# UI_mon.net
KiCad netlist of a schematic drawn in Altium Designer
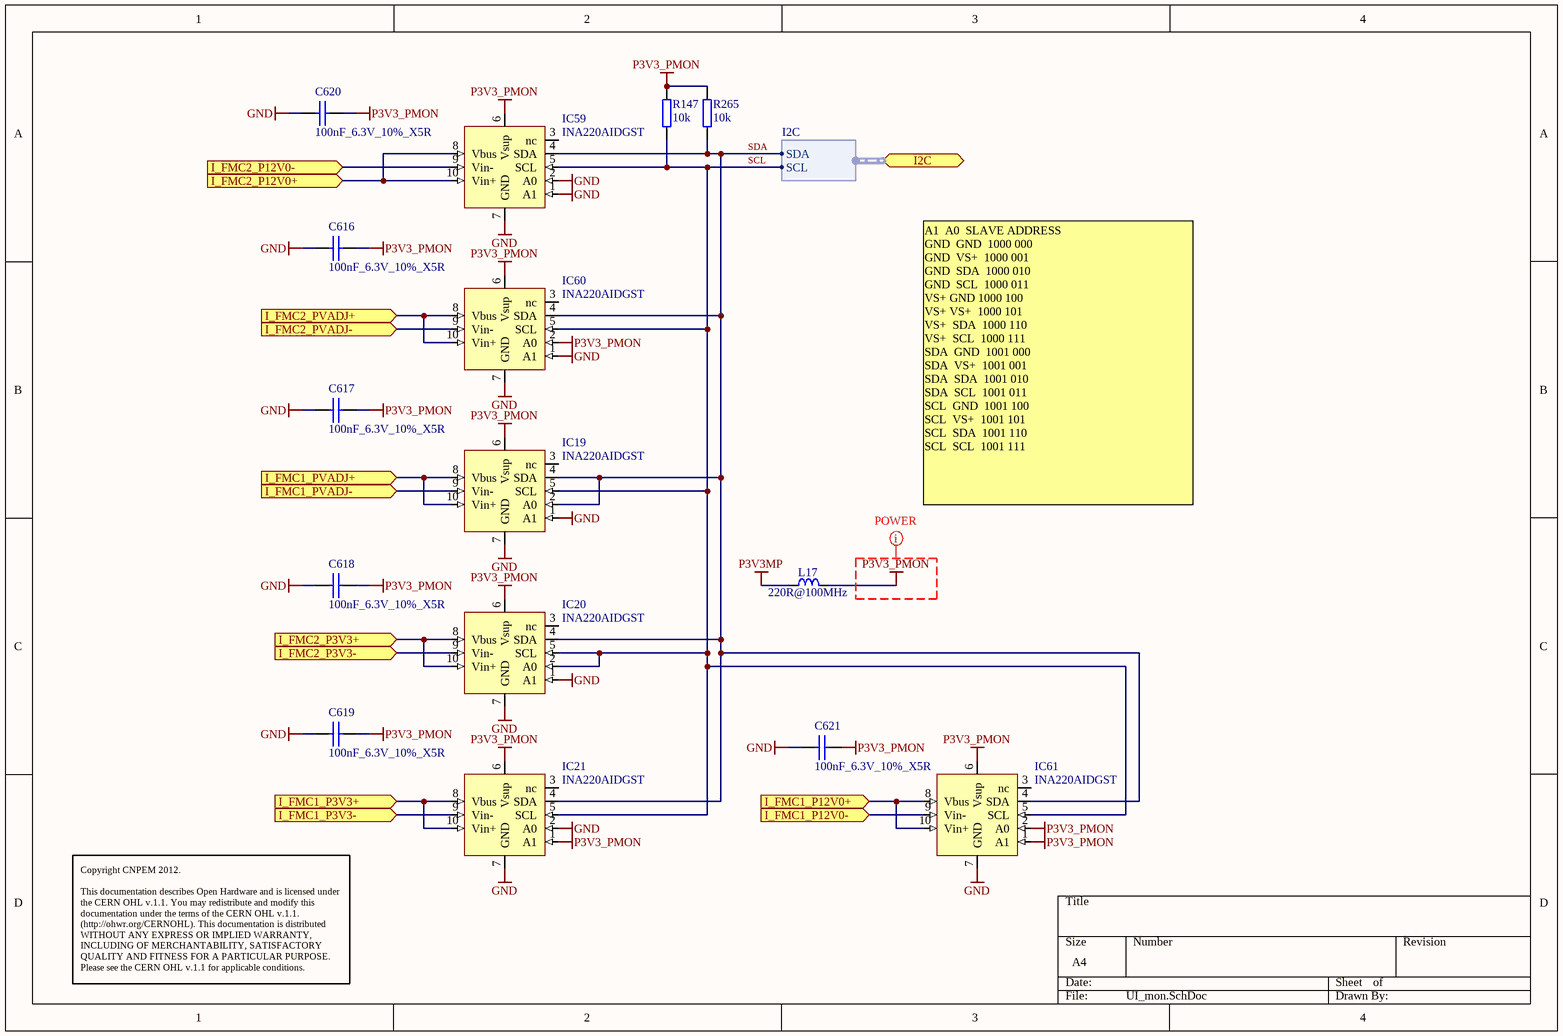
[diagram p0: UI_mon.SchDoc]

(export (version "E")
  (design (tool "Eeschema 10.0.6"))
  (components
    (comp (ref "C616")
      (value "100nF_6.3V_10%_X5R")
      (footprint "0201C")
      (description "Capacitor SMD")
      (libsource (lib "LIBRARY_SCH") (part "CAP_SMD_0201"))
    )
    (comp (ref "C617")
      (value "100nF_6.3V_10%_X5R")
      (footprint "0201C")
      (description "Capacitor SMD")
      (libsource (lib "LIBRARY_SCH") (part "CAP_SMD_0201"))
    )
    (comp (ref "C618")
      (value "100nF_6.3V_10%_X5R")
      (footprint "0201C")
      (description "Capacitor SMD")
      (libsource (lib "LIBRARY_SCH") (part "CAP_SMD_0201"))
    )
    (comp (ref "C619")
      (value "100nF_6.3V_10%_X5R")
      (footprint "0201C")
      (description "Capacitor SMD")
      (libsource (lib "LIBRARY_SCH") (part "CAP_SMD_0201"))
    )
    (comp (ref "C620")
      (value "100nF_6.3V_10%_X5R")
      (footprint "0201C")
      (description "Capacitor SMD")
      (libsource (lib "LIBRARY_SCH") (part "CAP_SMD_0201"))
    )
    (comp (ref "C621")
      (value "100nF_6.3V_10%_X5R")
      (footprint "0201C")
      (description "Capacitor SMD")
      (libsource (lib "LIBRARY_SCH") (part "CAP_SMD_0201"))
    )
    (comp (ref "IC19")
      (value "INA220AIDGST")
      (footprint "msop10")
      (description "CURRENT/POWER MONITOR with Two-Wire Interface")
      (libsource (lib "LIBRARY_SCH") (part "ADC_INA220"))
    )
    (comp (ref "IC20")
      (value "INA220AIDGST")
      (footprint "msop10")
      (description "CURRENT/POWER MONITOR with Two-Wire Interface")
      (libsource (lib "LIBRARY_SCH") (part "ADC_INA220"))
    )
    (comp (ref "IC21")
      (value "INA220AIDGST")
      (footprint "msop10")
      (description "CURRENT/POWER MONITOR with Two-Wire Interface")
      (libsource (lib "LIBRARY_SCH") (part "ADC_INA220"))
    )
    (comp (ref "IC59")
      (value "INA220AIDGST")
      (footprint "msop10")
      (description "CURRENT/POWER MONITOR with Two-Wire Interface")
      (libsource (lib "LIBRARY_SCH") (part "ADC_INA220"))
    )
    (comp (ref "IC60")
      (value "INA220AIDGST")
      (footprint "msop10")
      (description "CURRENT/POWER MONITOR with Two-Wire Interface")
      (libsource (lib "LIBRARY_SCH") (part "ADC_INA220"))
    )
    (comp (ref "IC61")
      (value "INA220AIDGST")
      (footprint "msop10")
      (description "CURRENT/POWER MONITOR with Two-Wire Interface")
      (libsource (lib "LIBRARY_SCH") (part "ADC_INA220"))
    )
    (comp (ref "L17")
      (value "220R@100MHz")
      (footprint "0603L")
      (description "Inductor")
      (fields
        (field (name "PART NUMBER") "IND0805_MURATA_BLM21PG221SN1D")
        (field (name "POWER") "2A")
        (field (name "AUTHOR") "CERN DEM JLC")
      )
      (libsource (lib "Inductors & Transformers") (part "Inductor"))
    )
    (comp (ref "R147")
      (value "10k")
      (footprint "0402R")
      (description "SMD Resistor")
      (libsource (lib "LIBRARY_SCH") (part "RES_0402"))
    )
    (comp (ref "R265")
      (value "10k")
      (footprint "0402R")
      (description "SMD Resistor")
      (libsource (lib "LIBRARY_SCH") (part "RES_0402"))
    )
  )
  (nets
    (net (code "2") (name "/I_FMC1_P3V3+") (class "Default")
      (node (ref "IC21") (pin "10") (pinfunction "Vin+_10") (pintype "input"))
      (node (ref "IC21") (pin "8") (pinfunction "Vbus_8") (pintype "input"))
    )
    (net (code "3") (name "/I_FMC1_P3V3-") (class "Default")
      (node (ref "IC21") (pin "9") (pinfunction "Vin-_9") (pintype "input"))
    )
    (net (code "4") (name "/I_FMC1_P12V0+") (class "Default")
      (node (ref "IC61") (pin "10") (pinfunction "Vin+_10") (pintype "input"))
      (node (ref "IC61") (pin "8") (pinfunction "Vbus_8") (pintype "input"))
    )
    (net (code "5") (name "/I_FMC1_P12V0-") (class "Default")
      (node (ref "IC61") (pin "9") (pinfunction "Vin-_9") (pintype "input"))
    )
    (net (code "6") (name "/I_FMC1_PVADJ+") (class "Default")
      (node (ref "IC19") (pin "10") (pinfunction "Vin+_10") (pintype "input"))
      (node (ref "IC19") (pin "8") (pinfunction "Vbus_8") (pintype "input"))
    )
    (net (code "7") (name "/I_FMC1_PVADJ-") (class "Default")
      (node (ref "IC19") (pin "9") (pinfunction "Vin-_9") (pintype "input"))
    )
    (net (code "8") (name "/I_FMC2_P3V3+") (class "Default")
      (node (ref "IC20") (pin "10") (pinfunction "Vin+_10") (pintype "input"))
      (node (ref "IC20") (pin "8") (pinfunction "Vbus_8") (pintype "input"))
    )
    (net (code "9") (name "/I_FMC2_P3V3-") (class "Default")
      (node (ref "IC20") (pin "9") (pinfunction "Vin-_9") (pintype "input"))
    )
    (net (code "10") (name "/I_FMC2_P12V0+") (class "Default")
      (node (ref "IC59") (pin "10") (pinfunction "Vin+_10") (pintype "input"))
      (node (ref "IC59") (pin "8") (pinfunction "Vbus_8") (pintype "input"))
    )
    (net (code "11") (name "/I_FMC2_P12V0-") (class "Default")
      (node (ref "IC59") (pin "9") (pinfunction "Vin-_9") (pintype "input"))
    )
    (net (code "12") (name "/I_FMC2_PVADJ+") (class "Default")
      (node (ref "IC60") (pin "10") (pinfunction "Vin+_10") (pintype "input"))
      (node (ref "IC60") (pin "8") (pinfunction "Vbus_8") (pintype "input"))
    )
    (net (code "13") (name "/I_FMC2_PVADJ-") (class "Default")
      (node (ref "IC60") (pin "9") (pinfunction "Vin-_9") (pintype "input"))
    )
    (net (code "14") (name "/SCL") (class "Default")
      (node (ref "IC19") (pin "5") (pinfunction "SCL_5") (pintype "input"))
      (node (ref "IC20") (pin "2") (pinfunction "A0_2") (pintype "input"))
      (node (ref "IC20") (pin "5") (pinfunction "SCL_5") (pintype "input"))
      (node (ref "IC21") (pin "5") (pinfunction "SCL_5") (pintype "input"))
      (node (ref "IC59") (pin "5") (pinfunction "SCL_5") (pintype "input"))
      (node (ref "IC60") (pin "5") (pinfunction "SCL_5") (pintype "input"))
      (node (ref "IC61") (pin "5") (pinfunction "SCL_5") (pintype "input"))
      (node (ref "R147") (pin "1") (pinfunction "1_1") (pintype "passive"))
    )
    (net (code "15") (name "/SDA") (class "Default")
      (node (ref "IC19") (pin "2") (pinfunction "A0_2") (pintype "input"))
      (node (ref "IC19") (pin "4") (pinfunction "SDA_4") (pintype "bidirectional"))
      (node (ref "IC20") (pin "4") (pinfunction "SDA_4") (pintype "bidirectional"))
      (node (ref "IC21") (pin "4") (pinfunction "SDA_4") (pintype "bidirectional"))
      (node (ref "IC59") (pin "4") (pinfunction "SDA_4") (pintype "bidirectional"))
      (node (ref "IC60") (pin "4") (pinfunction "SDA_4") (pintype "bidirectional"))
      (node (ref "IC61") (pin "4") (pinfunction "SDA_4") (pintype "bidirectional"))
      (node (ref "R265") (pin "1") (pinfunction "1_1") (pintype "passive"))
    )
    (net (code "17") (name "GND") (class "Default")
      (node (ref "C616") (pin "2") (pinfunction "2_2") (pintype "passive"))
      (node (ref "C617") (pin "2") (pinfunction "2_2") (pintype "passive"))
      (node (ref "C618") (pin "2") (pinfunction "2_2") (pintype "passive"))
      (node (ref "C619") (pin "2") (pinfunction "2_2") (pintype "passive"))
      (node (ref "C620") (pin "2") (pinfunction "2_2") (pintype "passive"))
      (node (ref "C621") (pin "2") (pinfunction "2_2") (pintype "passive"))
      (node (ref "IC19") (pin "1") (pinfunction "A1_1") (pintype "input"))
      (node (ref "IC19") (pin "7") (pinfunction "GND_7") (pintype "power_in"))
      (node (ref "IC20") (pin "1") (pinfunction "A1_1") (pintype "input"))
      (node (ref "IC20") (pin "7") (pinfunction "GND_7") (pintype "power_in"))
      (node (ref "IC21") (pin "2") (pinfunction "A0_2") (pintype "input"))
      (node (ref "IC21") (pin "7") (pinfunction "GND_7") (pintype "power_in"))
      (node (ref "IC59") (pin "1") (pinfunction "A1_1") (pintype "input"))
      (node (ref "IC59") (pin "2") (pinfunction "A0_2") (pintype "input"))
      (node (ref "IC59") (pin "7") (pinfunction "GND_7") (pintype "power_in"))
      (node (ref "IC60") (pin "1") (pinfunction "A1_1") (pintype "input"))
      (node (ref "IC60") (pin "7") (pinfunction "GND_7") (pintype "power_in"))
      (node (ref "IC61") (pin "7") (pinfunction "GND_7") (pintype "power_in"))
    )
    (net (code "18") (name "P3V3MP") (class "Default")
      (node (ref "L17") (pin "1") (pinfunction "1_1") (pintype "passive"))
    )
    (net (code "19") (name "P3V3_PMON") (class "Default")
      (node (ref "C616") (pin "1") (pinfunction "1_1") (pintype "passive"))
      (node (ref "C617") (pin "1") (pinfunction "1_1") (pintype "passive"))
      (node (ref "C618") (pin "1") (pinfunction "1_1") (pintype "passive"))
      (node (ref "C619") (pin "1") (pinfunction "1_1") (pintype "passive"))
      (node (ref "C620") (pin "1") (pinfunction "1_1") (pintype "passive"))
      (node (ref "C621") (pin "1") (pinfunction "1_1") (pintype "passive"))
      (node (ref "IC19") (pin "6") (pinfunction "Vsup_6") (pintype "power_in"))
      (node (ref "IC20") (pin "6") (pinfunction "Vsup_6") (pintype "power_in"))
      (node (ref "IC21") (pin "1") (pinfunction "A1_1") (pintype "input"))
      (node (ref "IC21") (pin "6") (pinfunction "Vsup_6") (pintype "power_in"))
      (node (ref "IC59") (pin "6") (pinfunction "Vsup_6") (pintype "power_in"))
      (node (ref "IC60") (pin "2") (pinfunction "A0_2") (pintype "input"))
      (node (ref "IC60") (pin "6") (pinfunction "Vsup_6") (pintype "power_in"))
      (node (ref "IC61") (pin "1") (pinfunction "A1_1") (pintype "input"))
      (node (ref "IC61") (pin "2") (pinfunction "A0_2") (pintype "input"))
      (node (ref "IC61") (pin "6") (pinfunction "Vsup_6") (pintype "power_in"))
      (node (ref "L17") (pin "2") (pinfunction "2_2") (pintype "passive"))
      (node (ref "R147") (pin "2") (pinfunction "2_2") (pintype "passive"))
      (node (ref "R265") (pin "2") (pinfunction "2_2") (pintype "passive"))
    )
    (net (code "20") (name "unconnected-(IC19-nc-Pad3)") (class "Default")
      (node (ref "IC19") (pin "3") (pinfunction "nc_3") (pintype "passive"))
    )
    (net (code "21") (name "unconnected-(IC20-nc-Pad3)") (class "Default")
      (node (ref "IC20") (pin "3") (pinfunction "nc_3") (pintype "passive"))
    )
    (net (code "22") (name "unconnected-(IC21-nc-Pad3)") (class "Default")
      (node (ref "IC21") (pin "3") (pinfunction "nc_3") (pintype "passive"))
    )
    (net (code "23") (name "unconnected-(IC59-nc-Pad3)") (class "Default")
      (node (ref "IC59") (pin "3") (pinfunction "nc_3") (pintype "passive"))
    )
    (net (code "24") (name "unconnected-(IC60-nc-Pad3)") (class "Default")
      (node (ref "IC60") (pin "3") (pinfunction "nc_3") (pintype "passive"))
    )
    (net (code "25") (name "unconnected-(IC61-nc-Pad3)") (class "Default")
      (node (ref "IC61") (pin "3") (pinfunction "nc_3") (pintype "passive"))
    )
  )
)
